# TopLevelDesign.net
KiCad netlist of a schematic drawn in Altium Designer
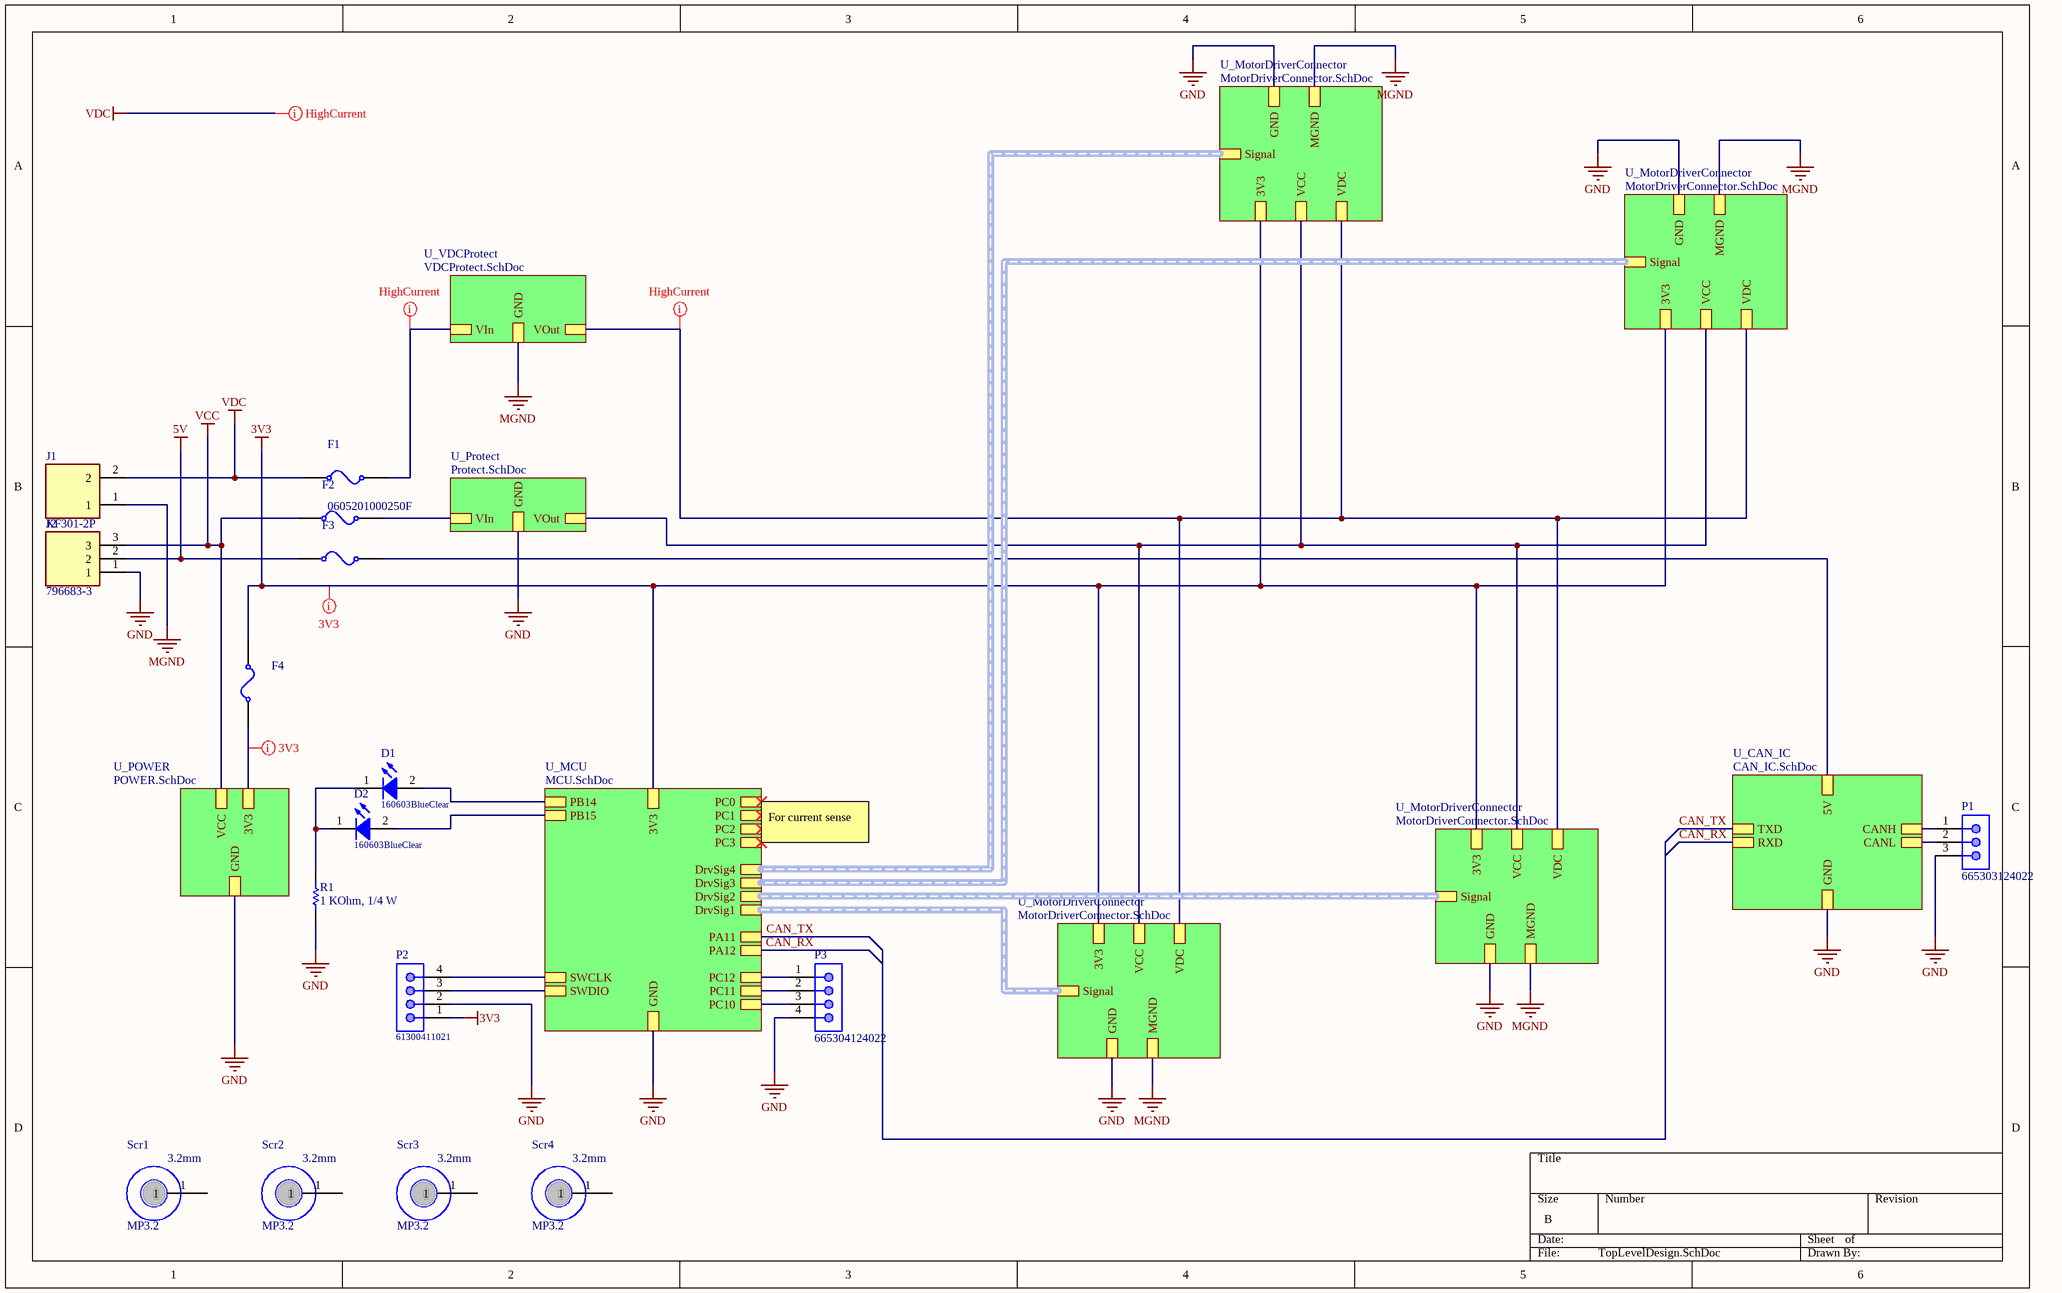
[diagram p0: TopLevelDesign.SchDoc]

(export (version "E")
  (design (tool "Eeschema 10.0.6"))
  (components
    (comp (ref "D1")
      (value "160603BlueClear")
      (footprint "WL-SMCW_0603_H=0.7mm")
      (description "WL-SMCW SMT Mono-color Chip LED Waterclear, size 0603, Blue, 3.2V, 140deg")
      (libsource (lib "Tin Tran") (part "160603BlueClear"))
    )
    (comp (ref "D2")
      (value "160603BlueClear")
      (footprint "WL-SMCW_0603_H=0.7mm")
      (description "WL-SMCW SMT Mono-color Chip LED Waterclear, size 0603, Blue, 3.2V, 140deg")
      (libsource (lib "Tin Tran") (part "160603BlueClear"))
    )
    (comp (ref "F1")
      (value "0605201000250F")
      (footprint "Fuse_Clip_0520")
      (description "Glass Fuse, Size 0520, 250 VAC, 10A, F")
      (fields (field (name "MANUFACTURER") "Littelfuse"))
      (libsource (lib "Tin Tran") (part "0605201000250F"))
    )
    (comp (ref "F2")
      (value "061812110024")
      (footprint "Fuse_SMD_1812")
      (description "Resettable Fuse, Size 1812, 24V, 1.1A")
      (fields (field (name "MANUFACTURER") "Bourns"))
      (libsource (lib "Tin Tran") (part "061812110024"))
    )
    (comp (ref "F3")
      (value "061812110024")
      (footprint "Fuse_SMD_1812")
      (description "Resettable Fuse, Size 1812, 24V, 1.1A")
      (fields (field (name "MANUFACTURER") "Bourns"))
      (libsource (lib "Tin Tran") (part "061812110024"))
    )
    (comp (ref "F4")
      (value "061812020030")
      (footprint "Fuse_SMD_1812")
      (description "Resettable Fuse, Size 1812, 30V, 0.2A")
      (fields (field (name "MANUFACTURER") "Bourns"))
      (libsource (lib "Tin Tran") (part "061812300006"))
    )
    (comp (ref "J1")
      (value "KF301-2P")
      (footprint "HANDSON_KF301-2P")
      (description "2 Pin Terminal Block 5mm Pitch")
      (libsource (lib "Tin Tran") (part "KF301-2P"))
    )
    (comp (ref "J2")
      (value "796683-3")
      (footprint "TE_796683-3")
      (description "Wire to Board 3 Position 5 mm Pitch 30-12 AWG Euro Style Terminal Block")
      (fields (field (name "MF") "TE Connectivity"))
      (libsource (lib "Tin Tran") (part "796683-3"))
    )
    (comp (ref "P1")
      (value "665303124022")
      (footprint "665303124022")
      (description "WR-WTB SMT Male Vertical Shrouded Header, pitch 1mm, 3p")
      (fields (field (name "PUBLISHER") "Wurth Elektronik"))
      (libsource (lib "Tin Tran") (part "665303124022"))
    )
    (comp (ref "P2")
      (value "61300411021")
      (footprint "61300411021")
      (description "WR-PHD Pin Header, THT, pitch 2.54mm, Single Row, Angled, 4p")
      (fields (field (name "MANUFACTURER") "Wurth Elektronik"))
      (libsource (lib "Tin Tran") (part "61300411121"))
    )
    (comp (ref "P3")
      (value "665304124022")
      (footprint "665304124022")
      (description "WR-WTB SMT Male Vertical Shrouded Header, pitch 1mm, 4p")
      (fields (field (name "PUBLISHER") "Wurth Elektronik"))
      (libsource (lib "Tin Tran") (part "665304124022"))
    )
    (comp (ref "R1")
      (value "1 KOhm, 1/4 W")
      (footprint "resistor_0603")
      (description "RES, size 0603, 1 KOhm, 1/4 W")
      (fields (field (name "Comment") "0006031021"))
      (libsource (lib "Tin Tran") (part "00060371541"))
    )
    (comp (ref "Scr1") (value "MP3.2") (footprint "MP3.2") (libsource (lib "Tin Tran") (part "MP3.2")))
    (comp (ref "Scr2") (value "MP3.2") (footprint "MP3.2") (libsource (lib "Tin Tran") (part "MP3.2")))
    (comp (ref "Scr3") (value "MP3.2") (footprint "MP3.2") (libsource (lib "Tin Tran") (part "MP3.2")))
    (comp (ref "Scr4") (value "MP3.2") (footprint "MP3.2") (libsource (lib "Tin Tran") (part "MP3.2")))
  )
  (nets
    (net (code "1") (name "/3V3") (class "Default")
      (node (ref "F4") (pin "0") (pinfunction "0_0") (pintype "passive"))
    )
    (net (code "2") (name "/5V") (class "Default")
      (node (ref "F3") (pin "1") (pinfunction "1_1") (pintype "passive"))
    )
    (net (code "3") (name "/CANH") (class "Default")
      (node (ref "P1") (pin "1") (pinfunction "1_1") (pintype "passive"))
    )
    (net (code "4") (name "/CANL") (class "Default")
      (node (ref "P1") (pin "2") (pinfunction "2_2") (pintype "passive"))
    )
    (net (code "11") (name "/PB14") (class "Default")
      (node (ref "D1") (pin "2") (pinfunction "A_2") (pintype "passive"))
    )
    (net (code "12") (name "/PB15") (class "Default")
      (node (ref "D2") (pin "2") (pinfunction "A_2") (pintype "passive"))
    )
    (net (code "17") (name "/PC10") (class "Default")
      (node (ref "P3") (pin "3") (pinfunction "3_3") (pintype "passive"))
    )
    (net (code "18") (name "/PC11") (class "Default")
      (node (ref "P3") (pin "2") (pinfunction "2_2") (pintype "passive"))
    )
    (net (code "19") (name "/PC12") (class "Default")
      (node (ref "P3") (pin "1") (pinfunction "1_1") (pintype "passive"))
    )
    (net (code "20") (name "/SWCLK") (class "Default")
      (node (ref "P2") (pin "4") (pinfunction "4_4") (pintype "passive"))
    )
    (net (code "21") (name "/SWDIO") (class "Default")
      (node (ref "P2") (pin "3") (pinfunction "3_3") (pintype "passive"))
    )
    (net (code "24") (name "/VIn") (class "Default")
      (node (ref "F1") (pin "1") (pinfunction "1_1") (pintype "passive"))
    )
    (net (code "25") (name "/VIn_1") (class "Default")
      (node (ref "F2") (pin "1") (pinfunction "1_1") (pintype "passive"))
    )
    (net (code "26") (name "3V3") (class "Default")
      (node (ref "F4") (pin "1") (pinfunction "1_1") (pintype "passive"))
      (node (ref "P2") (pin "1") (pinfunction "1_1") (pintype "passive"))
    )
    (net (code "27") (name "5V") (class "Default")
      (node (ref "F3") (pin "0") (pinfunction "0_0") (pintype "passive"))
      (node (ref "J2") (pin "2") (pinfunction "2_2") (pintype "passive"))
    )
    (net (code "28") (name "GND") (class "Default")
      (node (ref "J2") (pin "1") (pinfunction "1_1") (pintype "passive"))
      (node (ref "P1") (pin "3") (pinfunction "3_3") (pintype "passive"))
      (node (ref "P2") (pin "2") (pinfunction "2_2") (pintype "passive"))
      (node (ref "P3") (pin "4") (pinfunction "4_4") (pintype "passive"))
      (node (ref "R1") (pin "1") (pinfunction "1_1") (pintype "passive"))
    )
    (net (code "29") (name "MGND") (class "Default")
      (node (ref "J1") (pin "1") (pinfunction "1_1") (pintype "passive"))
    )
    (net (code "30") (name "Net-(D1-K)") (class "Default")
      (node (ref "D1") (pin "1") (pinfunction "K_1") (pintype "passive"))
      (node (ref "D2") (pin "1") (pinfunction "K_1") (pintype "passive"))
      (node (ref "R1") (pin "2") (pinfunction "2_2") (pintype "passive"))
    )
    (net (code "31") (name "VCC") (class "Default")
      (node (ref "F2") (pin "0") (pinfunction "0_0") (pintype "passive"))
      (node (ref "J2") (pin "3") (pinfunction "3_3") (pintype "passive"))
    )
    (net (code "32") (name "VDC") (class "Default")
      (node (ref "F1") (pin "0") (pinfunction "0_0") (pintype "passive"))
      (node (ref "J1") (pin "2") (pinfunction "2_2") (pintype "passive"))
    )
    (net (code "33") (name "unconnected-(Scr1-Pad1)") (class "Default")
      (node (ref "Scr1") (pin "1") (pinfunction "1_1") (pintype "passive"))
    )
    (net (code "34") (name "unconnected-(Scr2-Pad1)") (class "Default")
      (node (ref "Scr2") (pin "1") (pinfunction "1_1") (pintype "passive"))
    )
    (net (code "35") (name "unconnected-(Scr3-Pad1)") (class "Default")
      (node (ref "Scr3") (pin "1") (pinfunction "1_1") (pintype "passive"))
    )
    (net (code "36") (name "unconnected-(Scr4-Pad1)") (class "Default")
      (node (ref "Scr4") (pin "1") (pinfunction "1_1") (pintype "passive"))
    )
  )
)
